# controller_connect_board.net
KiCad netlist of a schematic drawn in EAGLE
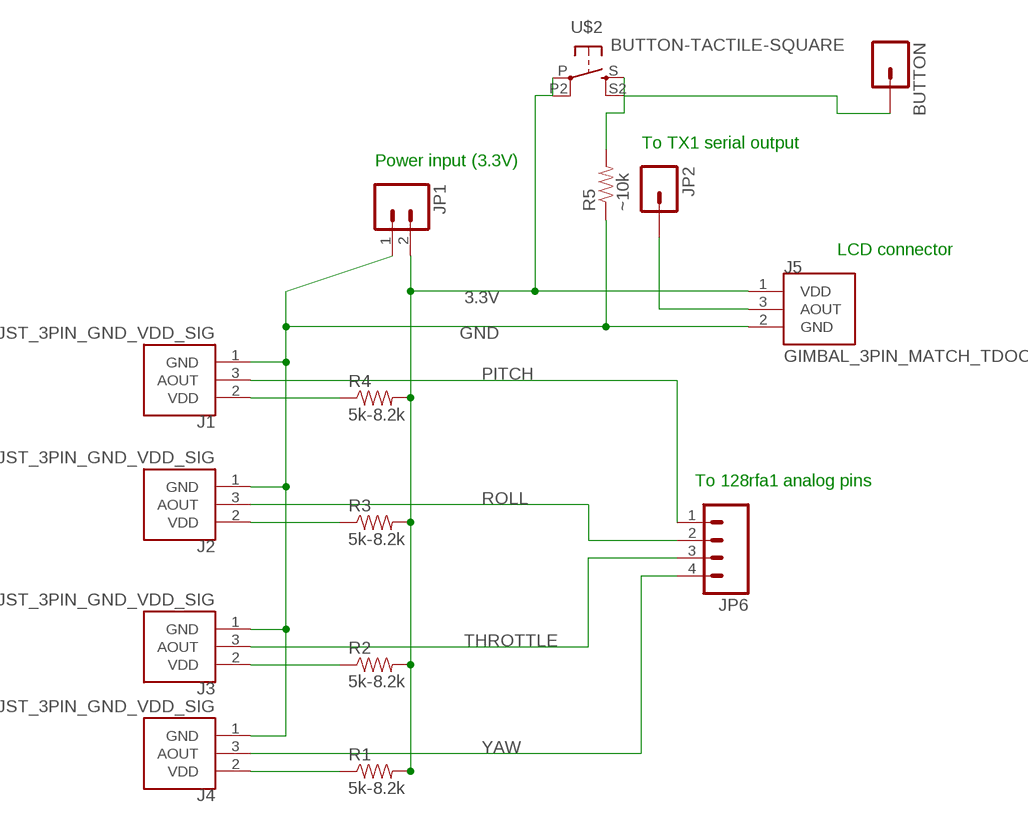
[diagram p0: schematic, sheet 1]

(export (version "E")
  (design (tool "Eeschema 10.0.6"))
  (components
    (comp (ref "BUTTON")
      (value "M01PTH")
      (footprint "eagle-import:1X01")
      (libsource (lib "eagle-import") (part "M01PTH"))
    )
    (comp (ref "J1")
      (value "JST_3PIN_GND_VDD_SIG")
      (footprint "eagle-import:JST-3-PTH-REVERSE")
      (libsource (lib "eagle-import") (part "JST_3PIN_GND_VDD_SIG"))
    )
    (comp (ref "J2")
      (value "JST_3PIN_GND_VDD_SIG")
      (footprint "eagle-import:JST-3-PTH-REVERSE")
      (libsource (lib "eagle-import") (part "JST_3PIN_GND_VDD_SIG"))
    )
    (comp (ref "J3")
      (value "JST_3PIN_GND_VDD_SIG")
      (footprint "eagle-import:JST-3-PTH-REVERSE")
      (libsource (lib "eagle-import") (part "JST_3PIN_GND_VDD_SIG"))
    )
    (comp (ref "J4")
      (value "JST_3PIN_GND_VDD_SIG")
      (footprint "eagle-import:JST-3-PTH-REVERSE")
      (libsource (lib "eagle-import") (part "JST_3PIN_GND_VDD_SIG"))
    )
    (comp (ref "J5")
      (value "GIMBAL_3PIN_MATCH_TDOCU")
      (footprint "eagle-import:JST-3-PTH")
      (libsource (lib "eagle-import") (part "GIMBAL_3PIN_MATCH_TDOCU"))
    )
    (comp (ref "JP1")
      (value "M021X02_NO_SILK")
      (footprint "eagle-import:1X02_NO_SILK")
      (libsource (lib "eagle-import") (part "M021X02_NO_SILK"))
    )
    (comp (ref "JP2")
      (value "M01PTH")
      (footprint "eagle-import:1X01")
      (libsource (lib "eagle-import") (part "M01PTH"))
    )
    (comp (ref "JP6")
      (value "M04PTH")
      (footprint "eagle-import:1X04")
      (libsource (lib "eagle-import") (part "M04PTH"))
    )
    (comp (ref "R1")
      (value "5k-8.2k")
      (footprint "eagle-import:AXIAL-0.4")
      (libsource (lib "eagle-import") (part "RESISTORPTH-1/4W"))
    )
    (comp (ref "R2")
      (value "5k-8.2k")
      (footprint "eagle-import:AXIAL-0.4")
      (libsource (lib "eagle-import") (part "RESISTORPTH-1/4W"))
    )
    (comp (ref "R3")
      (value "5k-8.2k")
      (footprint "eagle-import:AXIAL-0.4")
      (libsource (lib "eagle-import") (part "RESISTORPTH-1/4W"))
    )
    (comp (ref "R4")
      (value "5k-8.2k")
      (footprint "eagle-import:AXIAL-0.4")
      (libsource (lib "eagle-import") (part "RESISTORPTH-1/4W"))
    )
    (comp (ref "R5")
      (value "~10k")
      (footprint "eagle-import:AXIAL-0.4")
      (libsource (lib "eagle-import") (part "RESISTORPTH-1/4W"))
    )
    (comp (ref "U$2")
      (value "BUTTON-TACTILE-SQUARE")
      (footprint "eagle-import:BUTTON-TACTILE-SQUARE-ADAFRUIT1010")
      (libsource (lib "eagle-import") (part "BUTTON-TACTILE-SQUARE"))
    )
  )
  (nets
    (net (code "1") (name "/3.3V") (class "Default")
      (node (ref "J5") (pin "1") (pinfunction "VDD_1") (pintype "power_in"))
      (node (ref "JP1") (pin "2") (pinfunction "2_2") (pintype "passive"))
      (node (ref "R1") (pin "P$2") (pinfunction "2_P$2") (pintype "passive"))
      (node (ref "R2") (pin "P$2") (pinfunction "2_P$2") (pintype "passive"))
      (node (ref "R3") (pin "P$2") (pinfunction "2_P$2") (pintype "passive"))
      (node (ref "R4") (pin "P$2") (pinfunction "2_P$2") (pintype "passive"))
      (node (ref "U$2") (pin "P") (pinfunction "P_P") (pintype "passive"))
      (node (ref "U$2") (pin "P2") (pinfunction "P1_P2") (pintype "passive"))
    )
    (net (code "2") (name "/GND") (class "Default")
      (node (ref "J1") (pin "1") (pinfunction "GND_1") (pintype "power_in"))
      (node (ref "J2") (pin "1") (pinfunction "GND_1") (pintype "power_in"))
      (node (ref "J3") (pin "1") (pinfunction "GND_1") (pintype "power_in"))
      (node (ref "J4") (pin "1") (pinfunction "GND_1") (pintype "power_in"))
      (node (ref "J5") (pin "2") (pinfunction "GND_2") (pintype "power_in"))
      (node (ref "JP1") (pin "1") (pinfunction "1_1") (pintype "passive"))
      (node (ref "R5") (pin "P$1") (pinfunction "1_P$1") (pintype "passive"))
    )
    (net (code "3") (name "/PITCH") (class "Default")
      (node (ref "J1") (pin "3") (pinfunction "AOUT_3") (pintype "bidirectional"))
      (node (ref "JP6") (pin "1") (pinfunction "1_1") (pintype "passive"))
    )
    (net (code "4") (name "/ROLL") (class "Default")
      (node (ref "J2") (pin "3") (pinfunction "AOUT_3") (pintype "bidirectional"))
      (node (ref "JP6") (pin "2") (pinfunction "2_2") (pintype "passive"))
    )
    (net (code "5") (name "/THROTTLE") (class "Default")
      (node (ref "J3") (pin "3") (pinfunction "AOUT_3") (pintype "bidirectional"))
      (node (ref "JP6") (pin "3") (pinfunction "3_3") (pintype "passive"))
    )
    (net (code "6") (name "/YAW") (class "Default")
      (node (ref "J4") (pin "3") (pinfunction "AOUT_3") (pintype "bidirectional"))
      (node (ref "JP6") (pin "4") (pinfunction "4_4") (pintype "passive"))
    )
    (net (code "7") (name "Net-(J1-VDD)") (class "Default")
      (node (ref "J1") (pin "2") (pinfunction "VDD_2") (pintype "power_in"))
      (node (ref "R4") (pin "P$1") (pinfunction "1_P$1") (pintype "passive"))
    )
    (net (code "8") (name "Net-(J2-VDD)") (class "Default")
      (node (ref "J2") (pin "2") (pinfunction "VDD_2") (pintype "power_in"))
      (node (ref "R3") (pin "P$1") (pinfunction "1_P$1") (pintype "passive"))
    )
    (net (code "9") (name "Net-(J3-VDD)") (class "Default")
      (node (ref "J3") (pin "2") (pinfunction "VDD_2") (pintype "power_in"))
      (node (ref "R2") (pin "P$1") (pinfunction "1_P$1") (pintype "passive"))
    )
    (net (code "10") (name "Net-(J4-VDD)") (class "Default")
      (node (ref "J4") (pin "2") (pinfunction "VDD_2") (pintype "power_in"))
      (node (ref "R1") (pin "P$1") (pinfunction "1_P$1") (pintype "passive"))
    )
    (net (code "11") (name "Net-(J5-AOUT)") (class "Default")
      (node (ref "J5") (pin "3") (pinfunction "AOUT_3") (pintype "bidirectional"))
      (node (ref "JP2") (pin "1") (pinfunction "1_1") (pintype "passive"))
    )
    (net (code "12") (name "Net-(R5-2)") (class "Default")
      (node (ref "BUTTON") (pin "1") (pinfunction "1_1") (pintype "passive"))
      (node (ref "R5") (pin "P$2") (pinfunction "2_P$2") (pintype "passive"))
      (node (ref "U$2") (pin "S") (pinfunction "S_S") (pintype "passive"))
      (node (ref "U$2") (pin "S2") (pinfunction "S1_S2") (pintype "passive"))
    )
  )
)
